# 7805_SMD_0603.net
KiCad netlist of a schematic drawn in EAGLE
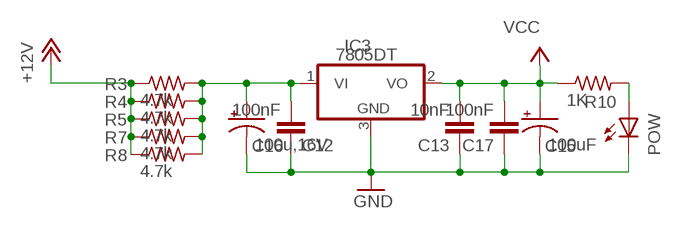
[diagram p0: schematic, sheet 1]

(export (version "E")
  (design (tool "Eeschema 10.0.6"))
  (components
    (comp (ref "C12")
      (value "100nF")
      (footprint "eagle-import:C0603")
      (libsource (lib "eagle-import") (part "C-EUC0603"))
    )
    (comp (ref "C13")
      (value "10nF")
      (footprint "eagle-import:C0603")
      (libsource (lib "eagle-import") (part "C-EUC0603"))
    )
    (comp (ref "C15")
      (value "100uF")
      (footprint "eagle-import:UD-6,3X7,7_NICHICON")
      (libsource (lib "eagle-import") (part "CPOL-USUD-6,3X7,7"))
    )
    (comp (ref "C16")
      (value "100u,16V")
      (footprint "eagle-import:UD-6,3X7,7_NICHICON")
      (libsource (lib "eagle-import") (part "CPOL-USUD-6,3X7,7"))
    )
    (comp (ref "C17")
      (value "100nF")
      (footprint "eagle-import:C0603")
      (libsource (lib "eagle-import") (part "C-EUC0603"))
    )
    (comp (ref "IC3")
      (value "7805DT")
      (footprint "eagle-import:TO252")
      (libsource (lib "eagle-import") (part "78DT05"))
    )
    (comp (ref "POW")
      (value "LEDCHIPLED_0603")
      (footprint "eagle-import:CHIPLED_0603")
      (libsource (lib "eagle-import") (part "LEDCHIPLED_0603"))
    )
    (comp (ref "R3")
      (value "4.7k")
      (footprint "eagle-import:R0603")
      (libsource (lib "eagle-import") (part "R-US_R0603"))
    )
    (comp (ref "R4")
      (value "4.7k")
      (footprint "eagle-import:R0603")
      (libsource (lib "eagle-import") (part "R-US_R0603"))
    )
    (comp (ref "R5")
      (value "4.7k")
      (footprint "eagle-import:R0603")
      (libsource (lib "eagle-import") (part "R-US_R0603"))
    )
    (comp (ref "R7")
      (value "4.7k")
      (footprint "eagle-import:R0603")
      (libsource (lib "eagle-import") (part "R-US_R0603"))
    )
    (comp (ref "R8")
      (value "4.7k")
      (footprint "eagle-import:R0603")
      (libsource (lib "eagle-import") (part "R-US_R0603"))
    )
    (comp (ref "R10")
      (value "1K")
      (footprint "eagle-import:R0603")
      (libsource (lib "eagle-import") (part "R-US_R0603"))
    )
  )
  (nets
    (net (code "1") (name "+12V") (class "Default")
      (node (ref "R3") (pin "1") (pinfunction "1_1") (pintype "passive"))
      (node (ref "R4") (pin "1") (pinfunction "1_1") (pintype "passive"))
      (node (ref "R5") (pin "1") (pinfunction "1_1") (pintype "passive"))
      (node (ref "R7") (pin "1") (pinfunction "1_1") (pintype "passive"))
      (node (ref "R8") (pin "1") (pinfunction "1_1") (pintype "passive"))
    )
    (net (code "2") (name "GND") (class "Default")
      (node (ref "C12") (pin "1") (pinfunction "1_1") (pintype "passive"))
      (node (ref "C13") (pin "1") (pinfunction "1_1") (pintype "passive"))
      (node (ref "C15") (pin "-") (pinfunction "-_-") (pintype "passive"))
      (node (ref "C16") (pin "-") (pinfunction "-_-") (pintype "passive"))
      (node (ref "C17") (pin "1") (pinfunction "1_1") (pintype "passive"))
      (node (ref "IC3") (pin "3") (pinfunction "GND_3") (pintype "passive"))
      (node (ref "POW") (pin "C") (pinfunction "C_C") (pintype "passive"))
    )
    (net (code "3") (name "Net-(IC3-VI)") (class "Default")
      (node (ref "C12") (pin "2") (pinfunction "2_2") (pintype "passive"))
      (node (ref "C16") (pin "+") (pinfunction "+_+") (pintype "passive"))
      (node (ref "IC3") (pin "1") (pinfunction "VI_1") (pintype "input"))
      (node (ref "R3") (pin "2") (pinfunction "2_2") (pintype "passive"))
      (node (ref "R4") (pin "2") (pinfunction "2_2") (pintype "passive"))
      (node (ref "R5") (pin "2") (pinfunction "2_2") (pintype "passive"))
      (node (ref "R7") (pin "2") (pinfunction "2_2") (pintype "passive"))
      (node (ref "R8") (pin "2") (pinfunction "2_2") (pintype "passive"))
    )
    (net (code "4") (name "Net-(POW-PadA)") (class "Default")
      (node (ref "POW") (pin "A") (pinfunction "A_A") (pintype "passive"))
      (node (ref "R10") (pin "2") (pinfunction "2_2") (pintype "passive"))
    )
    (net (code "5") (name "VCC") (class "Default")
      (node (ref "C13") (pin "2") (pinfunction "2_2") (pintype "passive"))
      (node (ref "C15") (pin "+") (pinfunction "+_+") (pintype "passive"))
      (node (ref "C17") (pin "2") (pinfunction "2_2") (pintype "passive"))
      (node (ref "IC3") (pin "2") (pinfunction "VO_2") (pintype "passive"))
      (node (ref "R10") (pin "1") (pinfunction "1_1") (pintype "passive"))
    )
  )
)
